# USBPort.net
KiCad netlist of a schematic drawn in Altium Designer
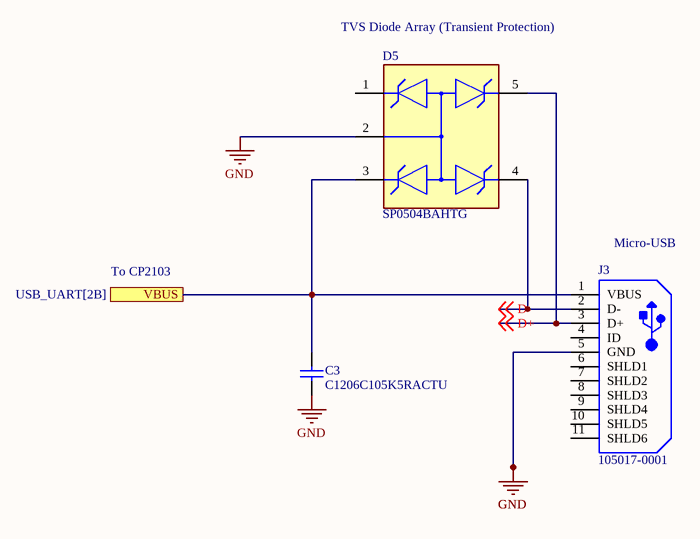
[diagram p0: USBPort.SchDoc]

(export (version "E")
  (design (tool "Eeschema 10.0.6"))
  (components
    (comp (ref "C3")
      (value "C1206C105K5RACTU")
      (footprint "CAPC3216X110X50LL20T25")
      (description "Chip Capacitor, 1 uF, +/- 10%, 50 V, -55 to 125 degC, 1206 (3216 Metric), RoHS, Tape and Reel")
      (fields (field (name "MANUFACTURER") "Kemet") (field (name "TOLERANCE") "10%"))
      (libsource (lib "Altium Content Vault") (part "CAP-NP-2"))
    )
    (comp (ref "D5")
      (value "SP0504BAHTG")
      (footprint "FP-SP0504BAHTG-MFG")
      (description "TVS DIODE 5.5V 8.5V SOT23-5")
      (fields
        (field (name "OCTOPART") "https://octopart.com/sp0504bahtg-littelfuse-587259")
        (field (name "MANUFACTURER") "Littelfuse")
      )
      (libsource (lib "Altium Content Vault") (part "766daeda9d65f3a5afe6095573230ef"))
    )
    (comp (ref "J3")
      (value "105017-0001")
      (footprint "USB-MICRO-B_V")
      (fields (field (name "MANUFACTURER") "Molex"))
      (libsource (lib "Altium Content Vault") (part "USB-5-6SHLD"))
    )
  )
  (nets
    (net (code "1") (name "/VBUS") (class "Default")
      (node (ref "C3") (pin "2") (pinfunction "2_2") (pintype "passive"))
      (node (ref "D5") (pin "3") (pinfunction "3_3") (pintype "passive"))
      (node (ref "J3") (pin "1") (pinfunction "VBUS_1") (pintype "passive"))
    )
    (net (code "2") (name "D+") (class "Default")
      (node (ref "D5") (pin "5") (pinfunction "5_5") (pintype "passive"))
      (node (ref "J3") (pin "3") (pinfunction "D+_3") (pintype "passive"))
    )
    (net (code "3") (name "D-") (class "Default")
      (node (ref "D5") (pin "4") (pinfunction "4_4") (pintype "passive"))
      (node (ref "J3") (pin "2") (pinfunction "D-_2") (pintype "passive"))
    )
    (net (code "4") (name "GND") (class "Default")
      (node (ref "C3") (pin "1") (pinfunction "1_1") (pintype "passive"))
      (node (ref "D5") (pin "2") (pinfunction "2_2") (pintype "passive"))
      (node (ref "J3") (pin "5") (pinfunction "GND_5") (pintype "passive"))
    )
    (net (code "5") (name "unconnected-(D5-Pad1)") (class "Default")
      (node (ref "D5") (pin "1") (pinfunction "1_1") (pintype "passive"))
    )
    (net (code "6") (name "unconnected-(J3-ID-Pad4)") (class "Default")
      (node (ref "J3") (pin "4") (pinfunction "ID_4") (pintype "passive"))
    )
    (net (code "7") (name "unconnected-(J3-SHLD1-Pad6)") (class "Default")
      (node (ref "J3") (pin "6") (pinfunction "SHLD1_6") (pintype "passive"))
    )
    (net (code "8") (name "unconnected-(J3-SHLD2-Pad7)") (class "Default")
      (node (ref "J3") (pin "7") (pinfunction "SHLD2_7") (pintype "passive"))
    )
    (net (code "9") (name "unconnected-(J3-SHLD3-Pad8)") (class "Default")
      (node (ref "J3") (pin "8") (pinfunction "SHLD3_8") (pintype "passive"))
    )
    (net (code "10") (name "unconnected-(J3-SHLD4-Pad9)") (class "Default")
      (node (ref "J3") (pin "9") (pinfunction "SHLD4_9") (pintype "passive"))
    )
    (net (code "11") (name "unconnected-(J3-SHLD5-Pad10)") (class "Default")
      (node (ref "J3") (pin "10") (pinfunction "SHLD5_10") (pintype "passive"))
    )
    (net (code "12") (name "unconnected-(J3-SHLD6-Pad11)") (class "Default")
      (node (ref "J3") (pin "11") (pinfunction "SHLD6_11") (pintype "passive"))
    )
  )
)
